# schaltplan_matrix2.net
KiCad netlist of a schematic drawn in EAGLE
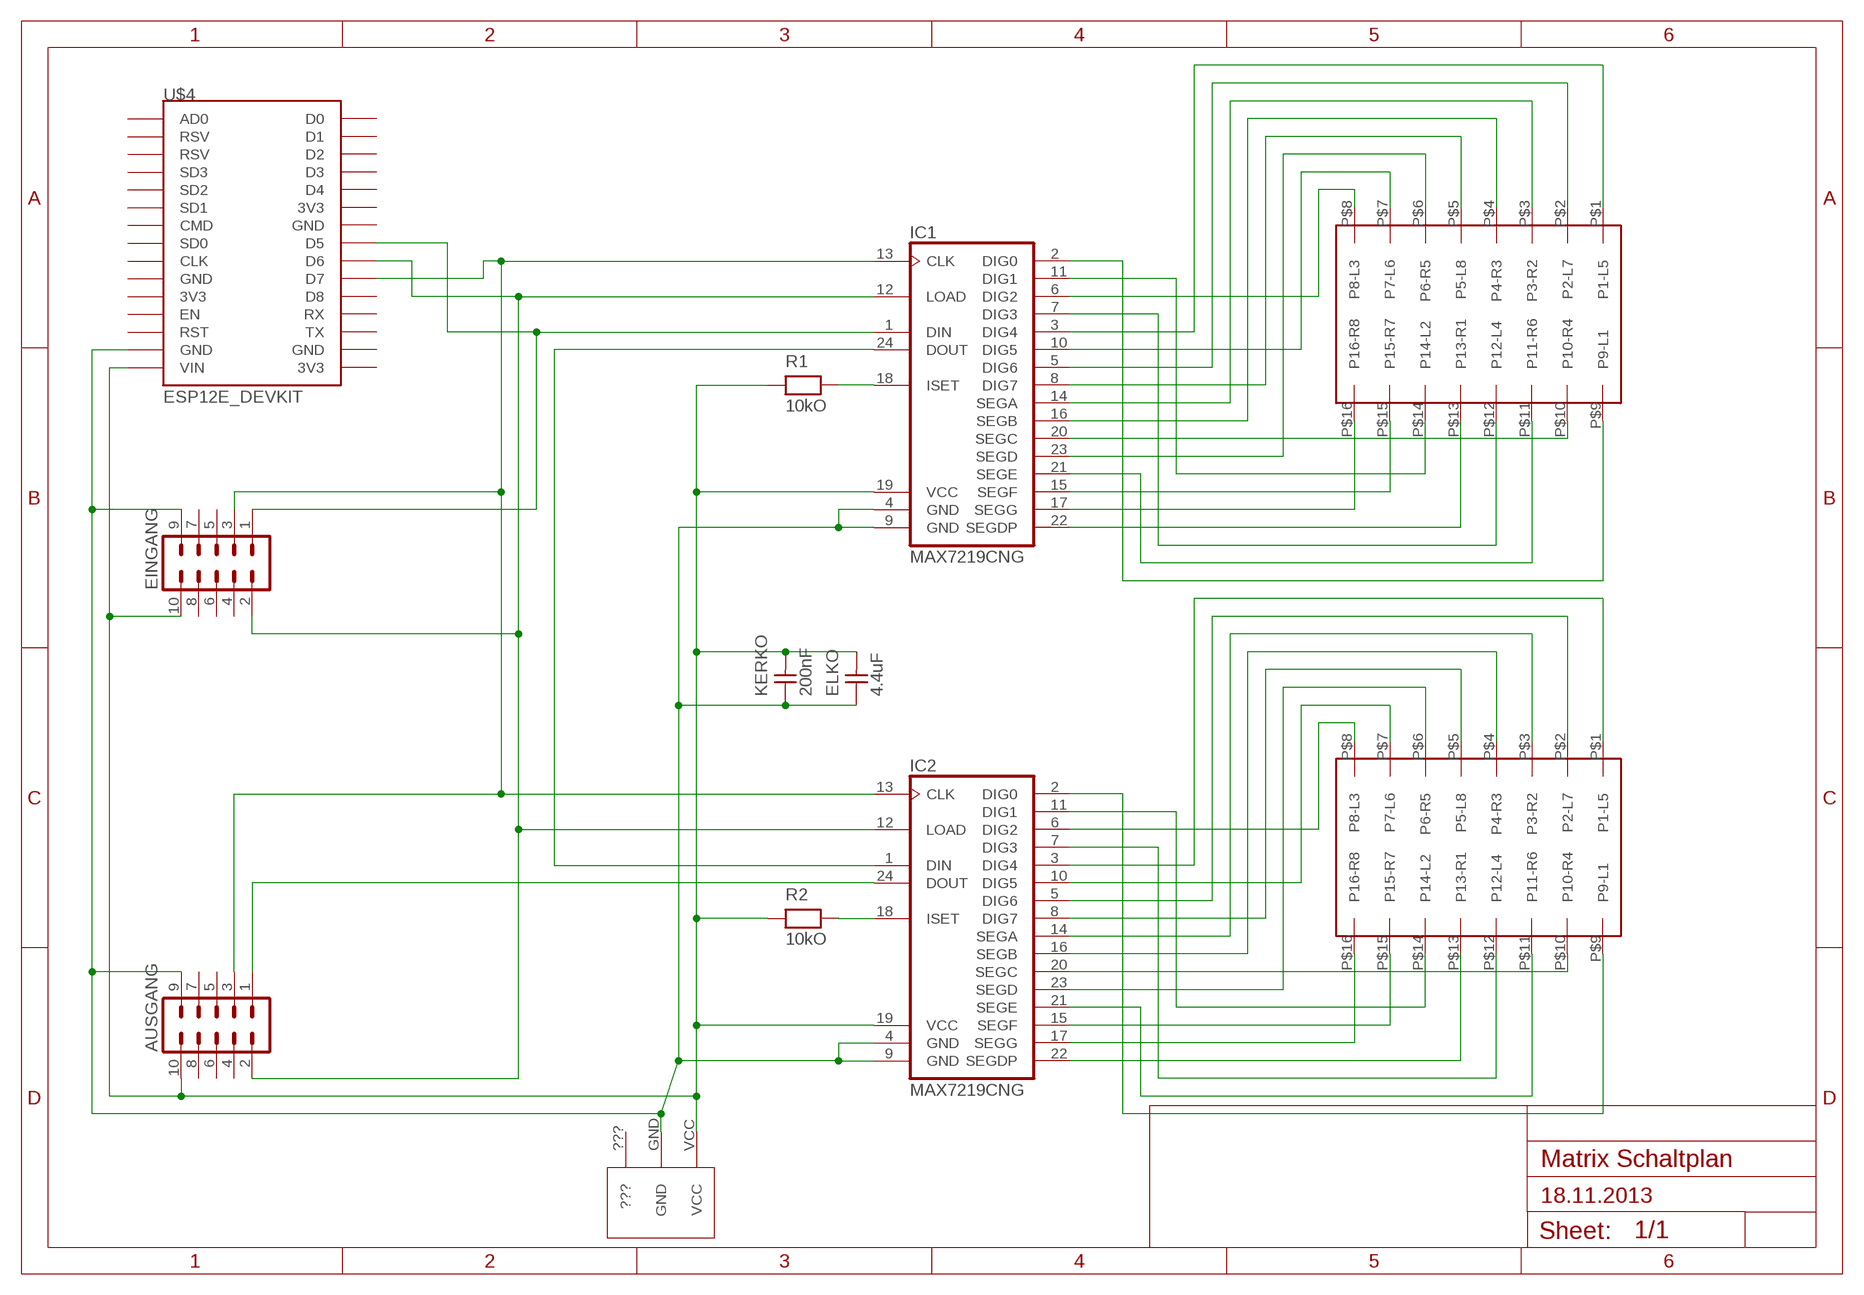
[diagram p0: schematic, sheet 1]

(export (version "E")
  (design (tool "Eeschema 10.0.6"))
  (components
    (comp (ref "AUSGANG")
      (value "ML10")
      (footprint "eagle-import:ML10")
      (libsource (lib "eagle-import") (part "ML10"))
    )
    (comp (ref "EINGANG")
      (value "ML10")
      (footprint "eagle-import:ML10")
      (libsource (lib "eagle-import") (part "ML10"))
    )
    (comp (ref "ELKO")
      (value "4.4uF")
      (footprint "eagle-import:C-5")
      (libsource (lib "eagle-import") (part "CAPNP-5"))
    )
    (comp (ref "IC1")
      (value "MAX7219CNG")
      (footprint "eagle-import:DIL24-3")
      (fields (field (name "MF") "MAXIM"))
      (libsource (lib "eagle-import") (part "MAX7219CNG"))
    )
    (comp (ref "IC2")
      (value "MAX7219CNG")
      (footprint "eagle-import:DIL24-3")
      (fields (field (name "MF") "MAXIM"))
      (libsource (lib "eagle-import") (part "MAX7219CNG"))
    )
    (comp (ref "KERKO")
      (value "200nF")
      (footprint "eagle-import:C-5")
      (libsource (lib "eagle-import") (part "CAPNP-5"))
    )
    (comp (ref "R1")
      (value "10kO")
      (footprint "eagle-import:R-5")
      (libsource (lib "eagle-import") (part "RESEU-5"))
    )
    (comp (ref "R2")
      (value "10kO")
      (footprint "eagle-import:R-5")
      (libsource (lib "eagle-import") (part "RESEU-5"))
    )
    (comp (ref "U$1")
      (value "MATRIX")
      (footprint "eagle-import:MATRIX")
      (libsource (lib "eagle-import") (part "MATRIX"))
    )
    (comp (ref "U$2")
      (value "MATRIX")
      (footprint "eagle-import:MATRIX")
      (libsource (lib "eagle-import") (part "MATRIX"))
    )
    (comp (ref "U$3")
      (value "LUM1613-18")
      (footprint "eagle-import:LUM16113-18")
      (libsource (lib "eagle-import") (part "LUM1613-18"))
    )
    (comp (ref "U$4")
      (value "ESP12E_DEVKIT")
      (footprint "eagle-import:ESP12E_DEVKIT")
      (libsource (lib "eagle-import") (part "ESP12E_DEVKIT"))
    )
  )
  (nets
    (net (code "1") (name "/???") (class "Default")
      (node (ref "U$3") (pin "???") (pinfunction "???_???") (pintype "power_in"))
    )
    (net (code "2") (name "Net-(AUSGANG-Pad9)") (class "Default")
      (node (ref "AUSGANG") (pin "9") (pinfunction "9_9") (pintype "passive"))
      (node (ref "EINGANG") (pin "9") (pinfunction "9_9") (pintype "passive"))
      (node (ref "ELKO") (pin "1") (pinfunction "1_1") (pintype "passive"))
      (node (ref "IC1") (pin "4") (pinfunction "GND_4") (pintype "power_in"))
      (node (ref "IC1") (pin "9") (pinfunction "GND_9") (pintype "power_in"))
      (node (ref "IC2") (pin "4") (pinfunction "GND_4") (pintype "power_in"))
      (node (ref "IC2") (pin "9") (pinfunction "GND_9") (pintype "power_in"))
      (node (ref "KERKO") (pin "1") (pinfunction "1_1") (pintype "passive"))
      (node (ref "U$3") (pin "GND") (pinfunction "GND_GND") (pintype "power_in"))
      (node (ref "U$4") (pin "GND@1") (pinfunction "GND_GND@1") (pintype "bidirectional"))
    )
    (net (code "3") (name "Net-(IC1-CLK)") (class "Default")
      (node (ref "AUSGANG") (pin "3") (pinfunction "3_3") (pintype "passive"))
      (node (ref "EINGANG") (pin "3") (pinfunction "3_3") (pintype "passive"))
      (node (ref "IC1") (pin "13") (pinfunction "CLK_13") (pintype "input"))
      (node (ref "IC2") (pin "13") (pinfunction "CLK_13") (pintype "input"))
      (node (ref "U$4") (pin "D7") (pinfunction "D7_D7") (pintype "bidirectional"))
    )
    (net (code "4") (name "Net-(IC1-DIG0)") (class "Default")
      (node (ref "IC1") (pin "2") (pinfunction "DIG0_2") (pintype "output"))
      (node (ref "U$1") (pin "P$9") (pinfunction "P9-L1_P$9") (pintype "bidirectional"))
    )
    (net (code "5") (name "Net-(IC1-DIG1)") (class "Default")
      (node (ref "IC1") (pin "11") (pinfunction "DIG1_11") (pintype "output"))
      (node (ref "U$1") (pin "P$14") (pinfunction "P14-L2_P$14") (pintype "bidirectional"))
    )
    (net (code "6") (name "Net-(IC1-DIG2)") (class "Default")
      (node (ref "IC1") (pin "6") (pinfunction "DIG2_6") (pintype "output"))
      (node (ref "U$1") (pin "P$8") (pinfunction "P8-L3_P$8") (pintype "bidirectional"))
    )
    (net (code "7") (name "Net-(IC1-DIG3)") (class "Default")
      (node (ref "IC1") (pin "7") (pinfunction "DIG3_7") (pintype "output"))
      (node (ref "U$1") (pin "P$12") (pinfunction "P12-L4_P$12") (pintype "bidirectional"))
    )
    (net (code "8") (name "Net-(IC1-DIG4)") (class "Default")
      (node (ref "IC1") (pin "3") (pinfunction "DIG4_3") (pintype "output"))
      (node (ref "U$1") (pin "P$1") (pinfunction "P1-L5_P$1") (pintype "bidirectional"))
    )
    (net (code "9") (name "Net-(IC1-DIG5)") (class "Default")
      (node (ref "IC1") (pin "10") (pinfunction "DIG5_10") (pintype "output"))
      (node (ref "U$1") (pin "P$7") (pinfunction "P7-L6_P$7") (pintype "bidirectional"))
    )
    (net (code "10") (name "Net-(IC1-DIG6)") (class "Default")
      (node (ref "IC1") (pin "5") (pinfunction "DIG6_5") (pintype "output"))
      (node (ref "U$1") (pin "P$2") (pinfunction "P2-L7_P$2") (pintype "bidirectional"))
    )
    (net (code "11") (name "Net-(IC1-DIG7)") (class "Default")
      (node (ref "IC1") (pin "8") (pinfunction "DIG7_8") (pintype "output"))
      (node (ref "U$1") (pin "P$5") (pinfunction "P5-L8_P$5") (pintype "bidirectional"))
    )
    (net (code "12") (name "Net-(IC1-DIN)") (class "Default")
      (node (ref "EINGANG") (pin "1") (pinfunction "1_1") (pintype "passive"))
      (node (ref "IC1") (pin "1") (pinfunction "DIN_1") (pintype "input"))
      (node (ref "U$4") (pin "D5") (pinfunction "D5_D5") (pintype "bidirectional"))
    )
    (net (code "13") (name "Net-(IC1-DOUT)") (class "Default")
      (node (ref "IC1") (pin "24") (pinfunction "DOUT_24") (pintype "output"))
      (node (ref "IC2") (pin "1") (pinfunction "DIN_1") (pintype "input"))
    )
    (net (code "14") (name "Net-(IC1-ISET)") (class "Default")
      (node (ref "IC1") (pin "18") (pinfunction "ISET_18") (pintype "input"))
      (node (ref "R1") (pin "2") (pinfunction "2_2") (pintype "passive"))
    )
    (net (code "15") (name "Net-(IC1-LOAD)") (class "Default")
      (node (ref "AUSGANG") (pin "2") (pinfunction "2_2") (pintype "passive"))
      (node (ref "EINGANG") (pin "2") (pinfunction "2_2") (pintype "passive"))
      (node (ref "IC1") (pin "12") (pinfunction "LOAD_12") (pintype "input"))
      (node (ref "IC2") (pin "12") (pinfunction "LOAD_12") (pintype "input"))
      (node (ref "U$4") (pin "D6") (pinfunction "D6_D6") (pintype "bidirectional"))
    )
    (net (code "16") (name "Net-(IC1-SEGA)") (class "Default")
      (node (ref "IC1") (pin "14") (pinfunction "SEGA_14") (pintype "output"))
      (node (ref "U$1") (pin "P$3") (pinfunction "P3-R2_P$3") (pintype "bidirectional"))
    )
    (net (code "17") (name "Net-(IC1-SEGB)") (class "Default")
      (node (ref "IC1") (pin "16") (pinfunction "SEGB_16") (pintype "output"))
      (node (ref "U$1") (pin "P$4") (pinfunction "P4-R3_P$4") (pintype "bidirectional"))
    )
    (net (code "18") (name "Net-(IC1-SEGC)") (class "Default")
      (node (ref "IC1") (pin "20") (pinfunction "SEGC_20") (pintype "output"))
      (node (ref "U$1") (pin "P$10") (pinfunction "P10-R4_P$10") (pintype "bidirectional"))
    )
    (net (code "19") (name "Net-(IC1-SEGD)") (class "Default")
      (node (ref "IC1") (pin "23") (pinfunction "SEGD_23") (pintype "output"))
      (node (ref "U$1") (pin "P$6") (pinfunction "P6-R5_P$6") (pintype "bidirectional"))
    )
    (net (code "20") (name "Net-(IC1-SEGDP)") (class "Default")
      (node (ref "IC1") (pin "22") (pinfunction "SEGDP_22") (pintype "output"))
      (node (ref "U$1") (pin "P$13") (pinfunction "P13-R1_P$13") (pintype "bidirectional"))
    )
    (net (code "21") (name "Net-(IC1-SEGE)") (class "Default")
      (node (ref "IC1") (pin "21") (pinfunction "SEGE_21") (pintype "output"))
      (node (ref "U$1") (pin "P$11") (pinfunction "P11-R6_P$11") (pintype "bidirectional"))
    )
    (net (code "22") (name "Net-(IC1-SEGF)") (class "Default")
      (node (ref "IC1") (pin "15") (pinfunction "SEGF_15") (pintype "output"))
      (node (ref "U$1") (pin "P$15") (pinfunction "P15-R7_P$15") (pintype "bidirectional"))
    )
    (net (code "23") (name "Net-(IC1-SEGG)") (class "Default")
      (node (ref "IC1") (pin "17") (pinfunction "SEGG_17") (pintype "output"))
      (node (ref "U$1") (pin "P$16") (pinfunction "P16-R8_P$16") (pintype "bidirectional"))
    )
    (net (code "24") (name "Net-(IC1-VCC)") (class "Default")
      (node (ref "AUSGANG") (pin "10") (pinfunction "10_10") (pintype "passive"))
      (node (ref "EINGANG") (pin "10") (pinfunction "10_10") (pintype "passive"))
      (node (ref "ELKO") (pin "2") (pinfunction "2_2") (pintype "passive"))
      (node (ref "IC1") (pin "19") (pinfunction "VCC_19") (pintype "power_in"))
      (node (ref "IC2") (pin "19") (pinfunction "VCC_19") (pintype "power_in"))
      (node (ref "KERKO") (pin "2") (pinfunction "2_2") (pintype "passive"))
      (node (ref "R1") (pin "1") (pinfunction "1_1") (pintype "passive"))
      (node (ref "R2") (pin "1") (pinfunction "1_1") (pintype "passive"))
      (node (ref "U$3") (pin "VCC") (pinfunction "VCC_VCC") (pintype "power_in"))
      (node (ref "U$4") (pin "VIN") (pinfunction "VIN_VIN") (pintype "bidirectional"))
    )
    (net (code "25") (name "Net-(IC2-DIG0)") (class "Default")
      (node (ref "IC2") (pin "2") (pinfunction "DIG0_2") (pintype "output"))
      (node (ref "U$2") (pin "P$9") (pinfunction "P9-L1_P$9") (pintype "bidirectional"))
    )
    (net (code "26") (name "Net-(IC2-DIG1)") (class "Default")
      (node (ref "IC2") (pin "11") (pinfunction "DIG1_11") (pintype "output"))
      (node (ref "U$2") (pin "P$14") (pinfunction "P14-L2_P$14") (pintype "bidirectional"))
    )
    (net (code "27") (name "Net-(IC2-DIG2)") (class "Default")
      (node (ref "IC2") (pin "6") (pinfunction "DIG2_6") (pintype "output"))
      (node (ref "U$2") (pin "P$8") (pinfunction "P8-L3_P$8") (pintype "bidirectional"))
    )
    (net (code "28") (name "Net-(IC2-DIG3)") (class "Default")
      (node (ref "IC2") (pin "7") (pinfunction "DIG3_7") (pintype "output"))
      (node (ref "U$2") (pin "P$12") (pinfunction "P12-L4_P$12") (pintype "bidirectional"))
    )
    (net (code "29") (name "Net-(IC2-DIG4)") (class "Default")
      (node (ref "IC2") (pin "3") (pinfunction "DIG4_3") (pintype "output"))
      (node (ref "U$2") (pin "P$1") (pinfunction "P1-L5_P$1") (pintype "bidirectional"))
    )
    (net (code "30") (name "Net-(IC2-DIG5)") (class "Default")
      (node (ref "IC2") (pin "10") (pinfunction "DIG5_10") (pintype "output"))
      (node (ref "U$2") (pin "P$7") (pinfunction "P7-L6_P$7") (pintype "bidirectional"))
    )
    (net (code "31") (name "Net-(IC2-DIG6)") (class "Default")
      (node (ref "IC2") (pin "5") (pinfunction "DIG6_5") (pintype "output"))
      (node (ref "U$2") (pin "P$2") (pinfunction "P2-L7_P$2") (pintype "bidirectional"))
    )
    (net (code "32") (name "Net-(IC2-DIG7)") (class "Default")
      (node (ref "IC2") (pin "8") (pinfunction "DIG7_8") (pintype "output"))
      (node (ref "U$2") (pin "P$5") (pinfunction "P5-L8_P$5") (pintype "bidirectional"))
    )
    (net (code "33") (name "Net-(IC2-DOUT)") (class "Default")
      (node (ref "AUSGANG") (pin "1") (pinfunction "1_1") (pintype "passive"))
      (node (ref "IC2") (pin "24") (pinfunction "DOUT_24") (pintype "output"))
    )
    (net (code "34") (name "Net-(IC2-ISET)") (class "Default")
      (node (ref "IC2") (pin "18") (pinfunction "ISET_18") (pintype "input"))
      (node (ref "R2") (pin "2") (pinfunction "2_2") (pintype "passive"))
    )
    (net (code "35") (name "Net-(IC2-SEGA)") (class "Default")
      (node (ref "IC2") (pin "14") (pinfunction "SEGA_14") (pintype "output"))
      (node (ref "U$2") (pin "P$3") (pinfunction "P3-R2_P$3") (pintype "bidirectional"))
    )
    (net (code "36") (name "Net-(IC2-SEGB)") (class "Default")
      (node (ref "IC2") (pin "16") (pinfunction "SEGB_16") (pintype "output"))
      (node (ref "U$2") (pin "P$4") (pinfunction "P4-R3_P$4") (pintype "bidirectional"))
    )
    (net (code "37") (name "Net-(IC2-SEGC)") (class "Default")
      (node (ref "IC2") (pin "20") (pinfunction "SEGC_20") (pintype "output"))
      (node (ref "U$2") (pin "P$10") (pinfunction "P10-R4_P$10") (pintype "bidirectional"))
    )
    (net (code "38") (name "Net-(IC2-SEGD)") (class "Default")
      (node (ref "IC2") (pin "23") (pinfunction "SEGD_23") (pintype "output"))
      (node (ref "U$2") (pin "P$6") (pinfunction "P6-R5_P$6") (pintype "bidirectional"))
    )
    (net (code "39") (name "Net-(IC2-SEGDP)") (class "Default")
      (node (ref "IC2") (pin "22") (pinfunction "SEGDP_22") (pintype "output"))
      (node (ref "U$2") (pin "P$13") (pinfunction "P13-R1_P$13") (pintype "bidirectional"))
    )
    (net (code "40") (name "Net-(IC2-SEGE)") (class "Default")
      (node (ref "IC2") (pin "21") (pinfunction "SEGE_21") (pintype "output"))
      (node (ref "U$2") (pin "P$11") (pinfunction "P11-R6_P$11") (pintype "bidirectional"))
    )
    (net (code "41") (name "Net-(IC2-SEGF)") (class "Default")
      (node (ref "IC2") (pin "15") (pinfunction "SEGF_15") (pintype "output"))
      (node (ref "U$2") (pin "P$15") (pinfunction "P15-R7_P$15") (pintype "bidirectional"))
    )
    (net (code "42") (name "Net-(IC2-SEGG)") (class "Default")
      (node (ref "IC2") (pin "17") (pinfunction "SEGG_17") (pintype "output"))
      (node (ref "U$2") (pin "P$16") (pinfunction "P16-R8_P$16") (pintype "bidirectional"))
    )
    (net (code "43") (name "unconnected-(AUSGANG-Pad4)") (class "Default")
      (node (ref "AUSGANG") (pin "4") (pinfunction "4_4") (pintype "passive"))
    )
    (net (code "44") (name "unconnected-(AUSGANG-Pad5)") (class "Default")
      (node (ref "AUSGANG") (pin "5") (pinfunction "5_5") (pintype "passive"))
    )
    (net (code "45") (name "unconnected-(AUSGANG-Pad6)") (class "Default")
      (node (ref "AUSGANG") (pin "6") (pinfunction "6_6") (pintype "passive"))
    )
    (net (code "46") (name "unconnected-(AUSGANG-Pad7)") (class "Default")
      (node (ref "AUSGANG") (pin "7") (pinfunction "7_7") (pintype "passive"))
    )
    (net (code "47") (name "unconnected-(AUSGANG-Pad8)") (class "Default")
      (node (ref "AUSGANG") (pin "8") (pinfunction "8_8") (pintype "passive"))
    )
    (net (code "48") (name "unconnected-(EINGANG-Pad4)") (class "Default")
      (node (ref "EINGANG") (pin "4") (pinfunction "4_4") (pintype "passive"))
    )
    (net (code "49") (name "unconnected-(EINGANG-Pad5)") (class "Default")
      (node (ref "EINGANG") (pin "5") (pinfunction "5_5") (pintype "passive"))
    )
    (net (code "50") (name "unconnected-(EINGANG-Pad6)") (class "Default")
      (node (ref "EINGANG") (pin "6") (pinfunction "6_6") (pintype "passive"))
    )
    (net (code "51") (name "unconnected-(EINGANG-Pad7)") (class "Default")
      (node (ref "EINGANG") (pin "7") (pinfunction "7_7") (pintype "passive"))
    )
    (net (code "52") (name "unconnected-(EINGANG-Pad8)") (class "Default")
      (node (ref "EINGANG") (pin "8") (pinfunction "8_8") (pintype "passive"))
    )
    (net (code "53") (name "unconnected-(U$4-3V3-Pad3V3@0)") (class "Default")
      (node (ref "U$4") (pin "3V3@0") (pinfunction "3V3_3V3@0") (pintype "bidirectional"))
    )
    (net (code "54") (name "unconnected-(U$4-3V3-Pad3V3@1)") (class "Default")
      (node (ref "U$4") (pin "3V3@1") (pinfunction "3V3_3V3@1") (pintype "bidirectional"))
    )
    (net (code "55") (name "unconnected-(U$4-3V3-Pad3V3@2)") (class "Default")
      (node (ref "U$4") (pin "3V3@2") (pinfunction "3V3_3V3@2") (pintype "bidirectional"))
    )
    (net (code "56") (name "unconnected-(U$4-GND-PadGND@0)") (class "Default")
      (node (ref "U$4") (pin "GND@0") (pinfunction "GND_GND@0") (pintype "bidirectional"))
    )
    (net (code "57") (name "unconnected-(U$4-GND-PadGND@2)") (class "Default")
      (node (ref "U$4") (pin "GND@2") (pinfunction "GND_GND@2") (pintype "bidirectional"))
    )
    (net (code "58") (name "unconnected-(U$4-GND-PadGND@3)") (class "Default")
      (node (ref "U$4") (pin "GND@3") (pinfunction "GND_GND@3") (pintype "bidirectional"))
    )
    (net (code "59") (name "unconnected-(U$4-PadAD0)") (class "Default")
      (node (ref "U$4") (pin "AD0") (pinfunction "AD0_AD0") (pintype "bidirectional"))
    )
    (net (code "60") (name "unconnected-(U$4-PadCLK)") (class "Default")
      (node (ref "U$4") (pin "CLK") (pinfunction "CLK_CLK") (pintype "bidirectional"))
    )
    (net (code "61") (name "unconnected-(U$4-PadCMD)") (class "Default")
      (node (ref "U$4") (pin "CMD") (pinfunction "CMD_CMD") (pintype "bidirectional"))
    )
    (net (code "62") (name "unconnected-(U$4-PadD0)") (class "Default")
      (node (ref "U$4") (pin "D0") (pinfunction "D0_D0") (pintype "bidirectional"))
    )
    (net (code "63") (name "unconnected-(U$4-PadD1)") (class "Default")
      (node (ref "U$4") (pin "D1") (pinfunction "D1_D1") (pintype "bidirectional"))
    )
    (net (code "64") (name "unconnected-(U$4-PadD2)") (class "Default")
      (node (ref "U$4") (pin "D2") (pinfunction "D2_D2") (pintype "bidirectional"))
    )
    (net (code "65") (name "unconnected-(U$4-PadD3)") (class "Default")
      (node (ref "U$4") (pin "D3") (pinfunction "D3_D3") (pintype "bidirectional"))
    )
    (net (code "66") (name "unconnected-(U$4-PadD4)") (class "Default")
      (node (ref "U$4") (pin "D4") (pinfunction "D4_D4") (pintype "bidirectional"))
    )
    (net (code "67") (name "unconnected-(U$4-PadD8)") (class "Default")
      (node (ref "U$4") (pin "D8") (pinfunction "D8_D8") (pintype "bidirectional"))
    )
    (net (code "68") (name "unconnected-(U$4-PadEN)") (class "Default")
      (node (ref "U$4") (pin "EN") (pinfunction "EN_EN") (pintype "bidirectional"))
    )
    (net (code "69") (name "unconnected-(U$4-PadRST)") (class "Default")
      (node (ref "U$4") (pin "RST") (pinfunction "RST_RST") (pintype "bidirectional"))
    )
    (net (code "70") (name "unconnected-(U$4-PadRX)") (class "Default")
      (node (ref "U$4") (pin "RX") (pinfunction "RX_RX") (pintype "bidirectional"))
    )
    (net (code "71") (name "unconnected-(U$4-PadSD0)") (class "Default")
      (node (ref "U$4") (pin "SD0") (pinfunction "SD0_SD0") (pintype "bidirectional"))
    )
    (net (code "72") (name "unconnected-(U$4-PadSD1)") (class "Default")
      (node (ref "U$4") (pin "SD1") (pinfunction "SD1_SD1") (pintype "bidirectional"))
    )
    (net (code "73") (name "unconnected-(U$4-PadSD2)") (class "Default")
      (node (ref "U$4") (pin "SD2") (pinfunction "SD2_SD2") (pintype "bidirectional"))
    )
    (net (code "74") (name "unconnected-(U$4-PadSD3)") (class "Default")
      (node (ref "U$4") (pin "SD3") (pinfunction "SD3_SD3") (pintype "bidirectional"))
    )
    (net (code "75") (name "unconnected-(U$4-PadTX)") (class "Default")
      (node (ref "U$4") (pin "TX") (pinfunction "TX_TX") (pintype "bidirectional"))
    )
    (net (code "76") (name "unconnected-(U$4-RSV-PadRSV@0)") (class "Default")
      (node (ref "U$4") (pin "RSV@0") (pinfunction "RSV_RSV@0") (pintype "bidirectional"))
    )
    (net (code "77") (name "unconnected-(U$4-RSV-PadRSV@1)") (class "Default")
      (node (ref "U$4") (pin "RSV@1") (pinfunction "RSV_RSV@1") (pintype "bidirectional"))
    )
  )
)
